# monolithich.net
KiCad netlist of a schematic drawn in EAGLE
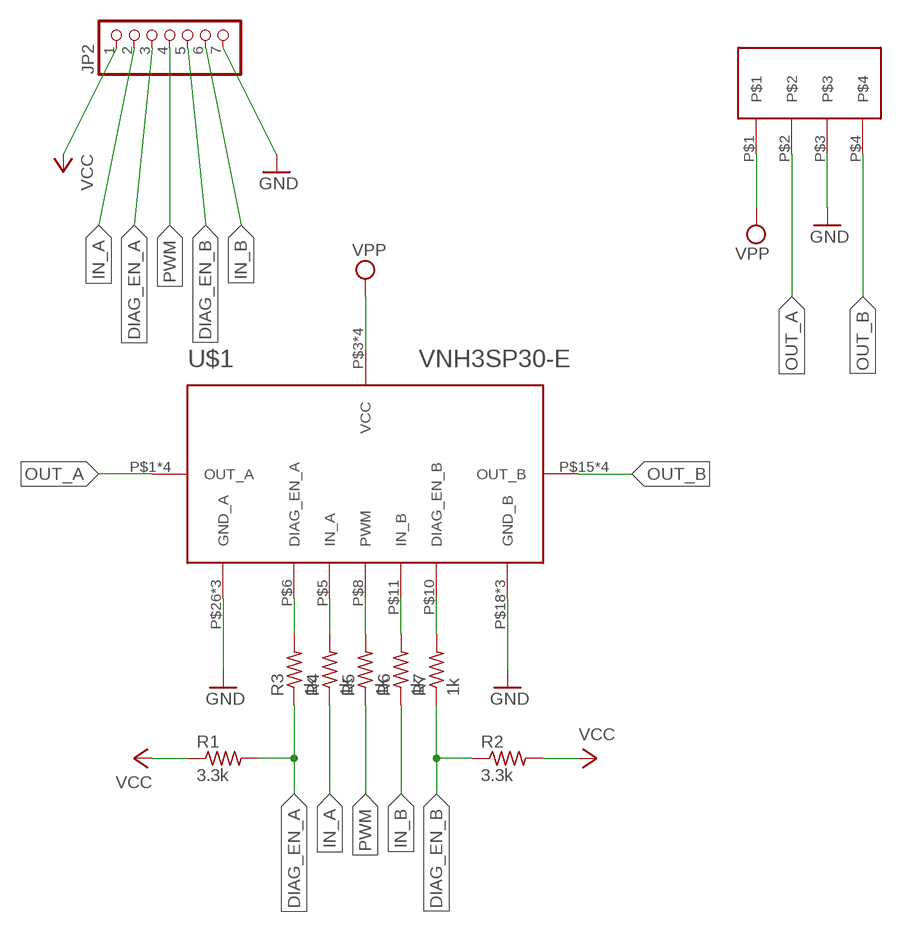
[diagram p0: schematic, sheet 1]

(export (version "E")
  (design (tool "Eeschema 10.0.6"))
  (components
    (comp (ref "JP2")
      (value "PINHD-1X7")
      (footprint "eagle-import:1X07")
      (libsource (lib "eagle-import") (part "PINHD-1X7"))
    )
    (comp (ref "R1")
      (value "3.3k")
      (footprint "eagle-import:R1206")
      (libsource (lib "eagle-import") (part "R-US_R1206"))
    )
    (comp (ref "R2")
      (value "3.3k")
      (footprint "eagle-import:R1206")
      (libsource (lib "eagle-import") (part "R-US_R1206"))
    )
    (comp (ref "R3")
      (value "1k")
      (footprint "eagle-import:R1206")
      (libsource (lib "eagle-import") (part "R-US_R1206"))
    )
    (comp (ref "R4")
      (value "1k")
      (footprint "eagle-import:R1206")
      (libsource (lib "eagle-import") (part "R-US_R1206"))
    )
    (comp (ref "R5")
      (value "1k")
      (footprint "eagle-import:R1206")
      (libsource (lib "eagle-import") (part "R-US_R1206"))
    )
    (comp (ref "R6")
      (value "1k")
      (footprint "eagle-import:R1206")
      (libsource (lib "eagle-import") (part "R-US_R1206"))
    )
    (comp (ref "R7")
      (value "1k")
      (footprint "eagle-import:R1206")
      (libsource (lib "eagle-import") (part "R-US_R1206"))
    )
    (comp (ref "U$1")
      (value "VNH3SP30-E")
      (footprint "eagle-import:MULTIPOWER-SO-30")
      (libsource (lib "eagle-import") (part "VNH3SP30-E"))
    )
    (comp (ref "U$2")
      (value "PINHEAD-5MM-1X4")
      (footprint "eagle-import:5MM-HEADER-4")
      (libsource (lib "eagle-import") (part "PINHEAD-5MM-1X4"))
    )
  )
  (nets
    (net (code "1") (name "DIAG_EN_A") (class "Default")
      (node (ref "JP2") (pin "3") (pinfunction "3_3") (pintype "passive"))
      (node (ref "R1") (pin "2") (pinfunction "2_2") (pintype "passive"))
      (node (ref "R3") (pin "1") (pinfunction "1_1") (pintype "passive"))
    )
    (net (code "2") (name "DIAG_EN_B") (class "Default")
      (node (ref "JP2") (pin "5") (pinfunction "5_5") (pintype "passive"))
      (node (ref "R2") (pin "1") (pinfunction "1_1") (pintype "passive"))
      (node (ref "R7") (pin "1") (pinfunction "1_1") (pintype "passive"))
    )
    (net (code "3") (name "GND") (class "Default")
      (node (ref "JP2") (pin "7") (pinfunction "7_7") (pintype "passive"))
      (node (ref "U$1") (pin "P$18") (pinfunction "GND_B_P$18") (pintype "bidirectional"))
      (node (ref "U$1") (pin "P$19") (pinfunction "GND_B_P$19") (pintype "bidirectional"))
      (node (ref "U$1") (pin "P$20") (pinfunction "GND_B_P$20") (pintype "bidirectional"))
      (node (ref "U$1") (pin "P$26") (pinfunction "GND_A_P$26") (pintype "bidirectional"))
      (node (ref "U$1") (pin "P$27") (pinfunction "GND_A_P$27") (pintype "bidirectional"))
      (node (ref "U$1") (pin "P$28") (pinfunction "GND_A_P$28") (pintype "bidirectional"))
      (node (ref "U$2") (pin "P$3") (pinfunction "P$3_P$3") (pintype "bidirectional"))
    )
    (net (code "4") (name "IN_A") (class "Default")
      (node (ref "JP2") (pin "2") (pinfunction "2_2") (pintype "passive"))
      (node (ref "R4") (pin "1") (pinfunction "1_1") (pintype "passive"))
    )
    (net (code "5") (name "IN_B") (class "Default")
      (node (ref "JP2") (pin "6") (pinfunction "6_6") (pintype "passive"))
      (node (ref "R6") (pin "1") (pinfunction "1_1") (pintype "passive"))
    )
    (net (code "6") (name "Net-(U$1-DIAG_EN_A)") (class "Default")
      (node (ref "R3") (pin "2") (pinfunction "2_2") (pintype "passive"))
      (node (ref "U$1") (pin "P$6") (pinfunction "DIAG_EN_A_P$6") (pintype "bidirectional"))
    )
    (net (code "7") (name "Net-(U$1-DIAG_EN_B)") (class "Default")
      (node (ref "R7") (pin "2") (pinfunction "2_2") (pintype "passive"))
      (node (ref "U$1") (pin "P$10") (pinfunction "DIAG_EN_B_P$10") (pintype "bidirectional"))
    )
    (net (code "8") (name "Net-(U$1-IN_A)") (class "Default")
      (node (ref "R4") (pin "2") (pinfunction "2_2") (pintype "passive"))
      (node (ref "U$1") (pin "P$5") (pinfunction "IN_A_P$5") (pintype "bidirectional"))
    )
    (net (code "9") (name "Net-(U$1-IN_B)") (class "Default")
      (node (ref "R6") (pin "2") (pinfunction "2_2") (pintype "passive"))
      (node (ref "U$1") (pin "P$11") (pinfunction "IN_B_P$11") (pintype "bidirectional"))
    )
    (net (code "10") (name "Net-(U$1-PWM)") (class "Default")
      (node (ref "R5") (pin "2") (pinfunction "2_2") (pintype "passive"))
      (node (ref "U$1") (pin "P$8") (pinfunction "PWM_P$8") (pintype "bidirectional"))
    )
    (net (code "11") (name "OUT_A") (class "Default")
      (node (ref "U$1") (pin "P$1") (pinfunction "OUT_A_P$1") (pintype "bidirectional"))
      (node (ref "U$1") (pin "P$25") (pinfunction "OUT_A_P$25") (pintype "bidirectional"))
      (node (ref "U$1") (pin "P$30") (pinfunction "OUT_A_P$30") (pintype "bidirectional"))
      (node (ref "U$1") (pin "T$1") (pinfunction "OUT_A_T$1") (pintype "bidirectional"))
      (node (ref "U$2") (pin "P$2") (pinfunction "P$2_P$2") (pintype "bidirectional"))
    )
    (net (code "12") (name "OUT_B") (class "Default")
      (node (ref "U$1") (pin "P$15") (pinfunction "OUT_B_P$15") (pintype "bidirectional"))
      (node (ref "U$1") (pin "P$16") (pinfunction "OUT_B_P$16") (pintype "bidirectional"))
      (node (ref "U$1") (pin "P$21") (pinfunction "OUT_B_P$21") (pintype "bidirectional"))
      (node (ref "U$1") (pin "T$2") (pinfunction "OUT_B_T$2") (pintype "bidirectional"))
      (node (ref "U$2") (pin "P$4") (pinfunction "P$4_P$4") (pintype "bidirectional"))
    )
    (net (code "13") (name "PWM") (class "Default")
      (node (ref "JP2") (pin "4") (pinfunction "4_4") (pintype "passive"))
      (node (ref "R5") (pin "1") (pinfunction "1_1") (pintype "passive"))
    )
    (net (code "14") (name "VCC") (class "Default")
      (node (ref "JP2") (pin "1") (pinfunction "1_1") (pintype "passive"))
      (node (ref "R1") (pin "1") (pinfunction "1_1") (pintype "passive"))
      (node (ref "R2") (pin "2") (pinfunction "2_2") (pintype "passive"))
    )
    (net (code "15") (name "VPP") (class "Default")
      (node (ref "U$1") (pin "P$13") (pinfunction "VCC_P$13") (pintype "bidirectional"))
      (node (ref "U$1") (pin "P$23") (pinfunction "VCC_P$23") (pintype "bidirectional"))
      (node (ref "U$1") (pin "P$3") (pinfunction "VCC_P$3") (pintype "bidirectional"))
      (node (ref "U$1") (pin "T$3") (pinfunction "VCC_T$3") (pintype "bidirectional"))
      (node (ref "U$2") (pin "P$1") (pinfunction "P$1_P$1") (pintype "bidirectional"))
    )
  )
)
